# H_Bridge.net
KiCad netlist of a schematic drawn in Altium Designer
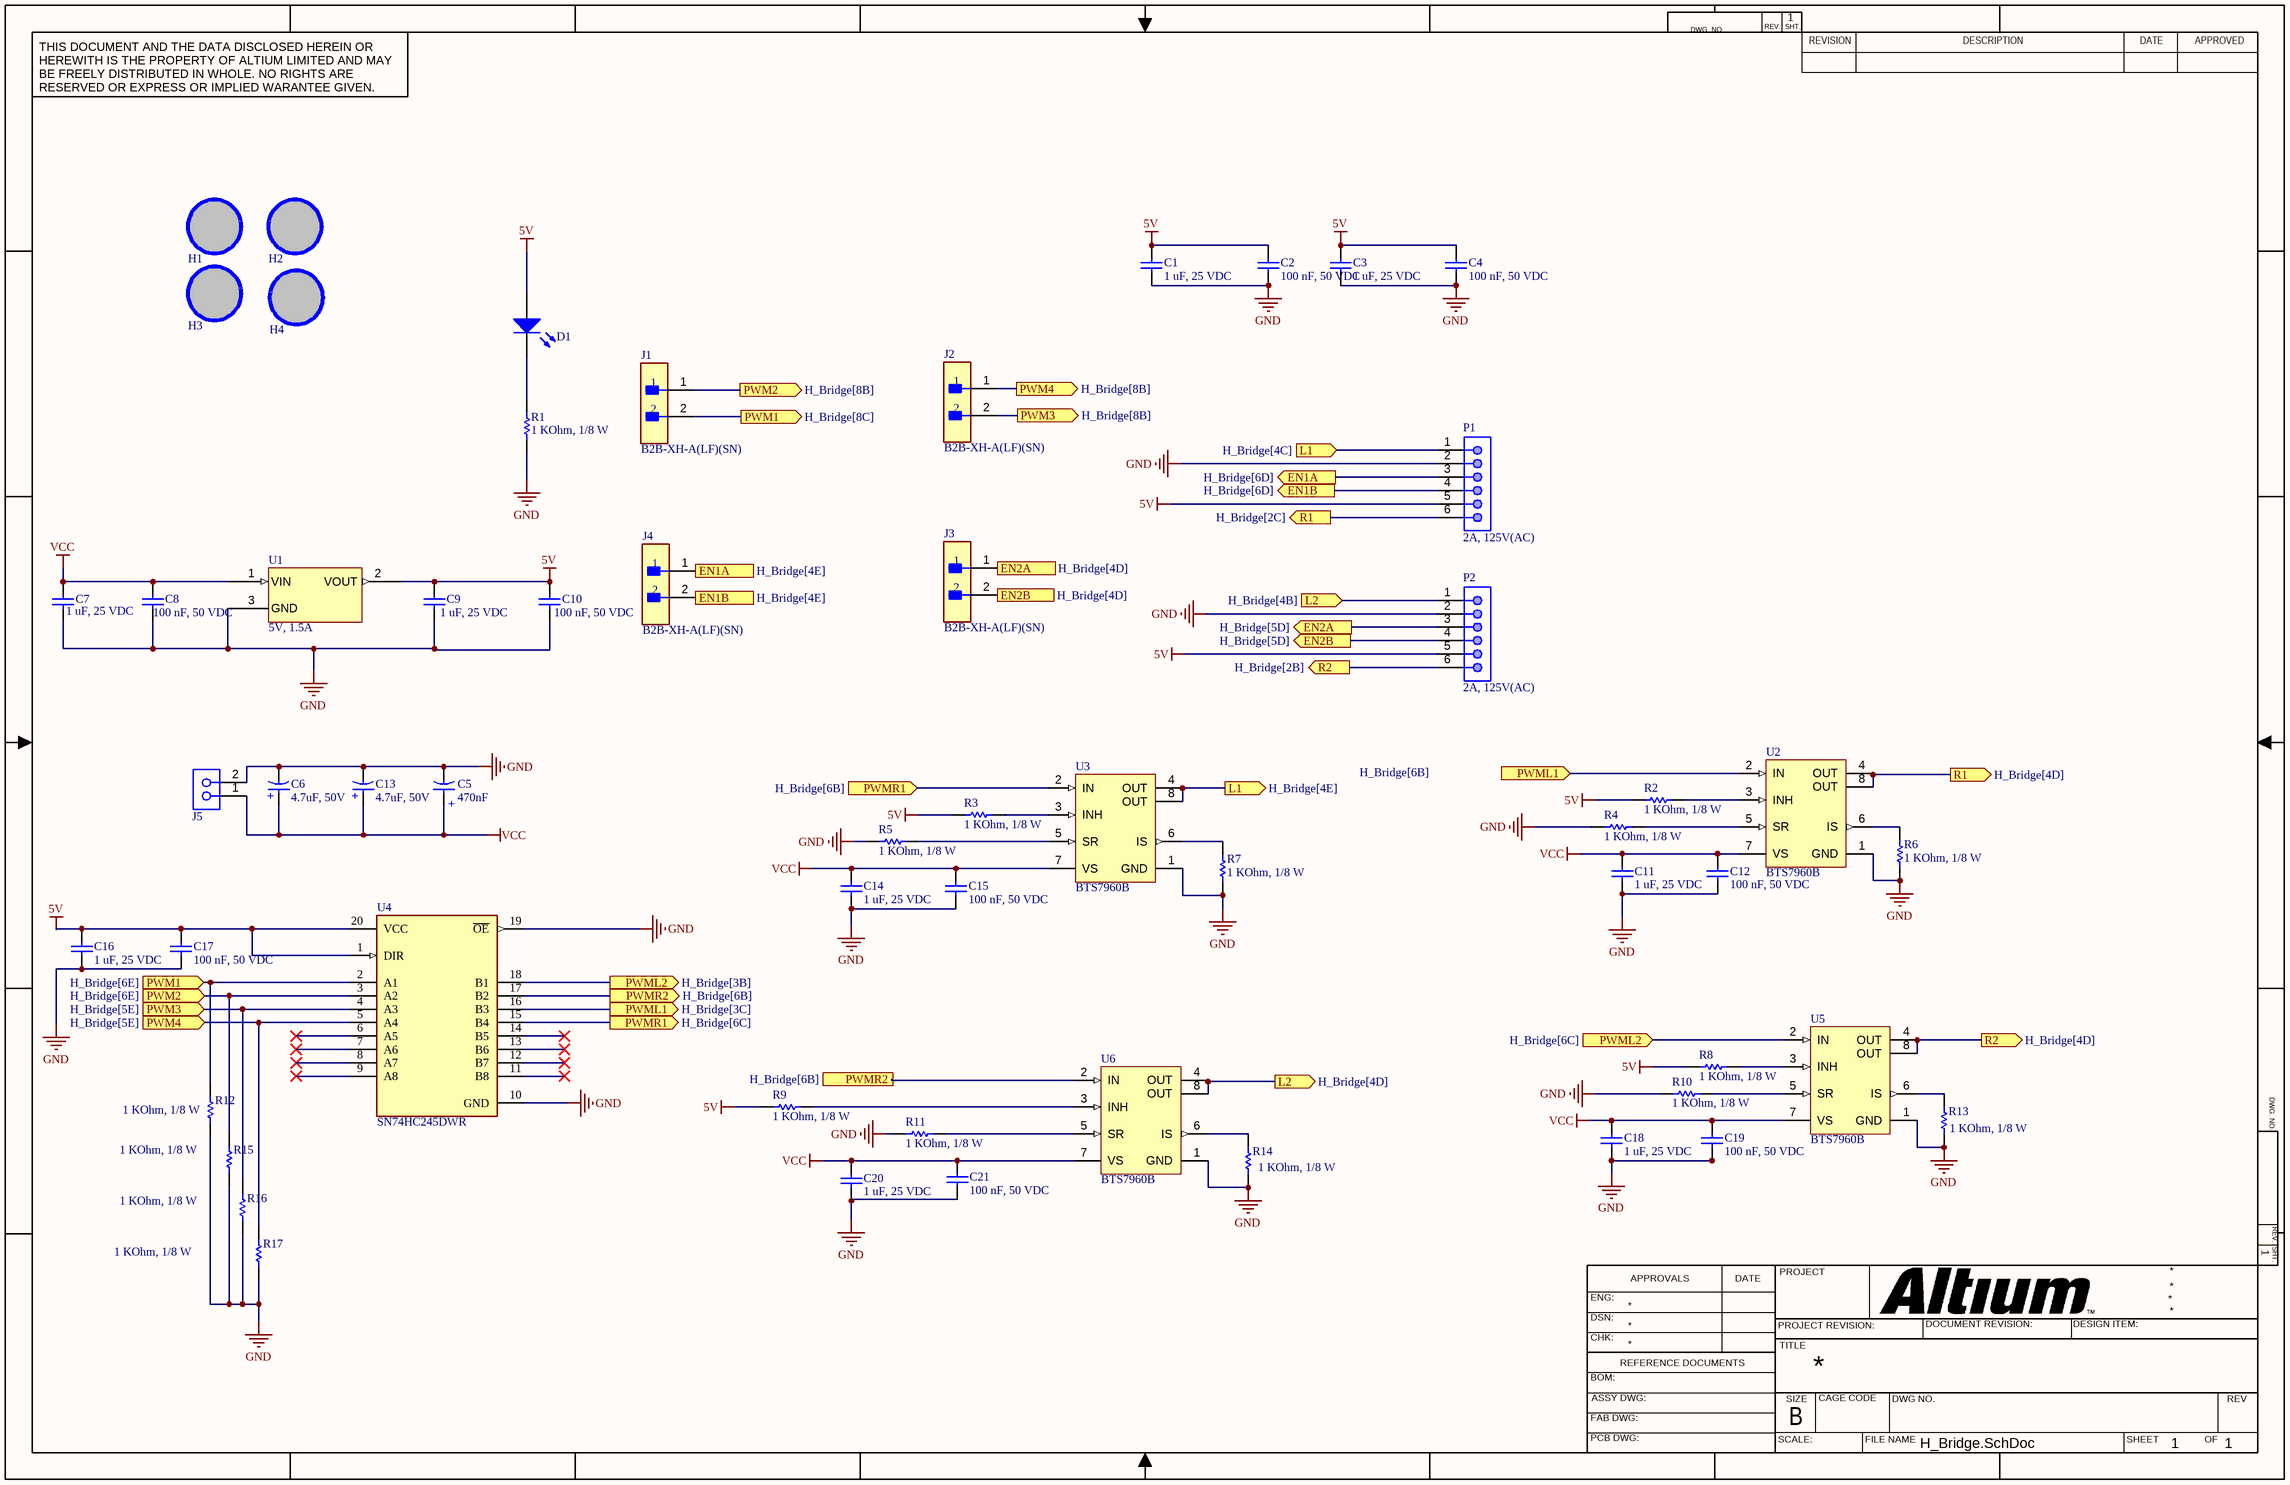
[diagram p0: H_Bridge.SchDoc]

(export (version "E")
  (design (tool "Eeschema 10.0.6"))
  (components
    (comp (ref "C1")
      (value "1 uF, 25 VDC")
      (footprint "CAP_0805")
      (description "CAP, size 0805, 1 uF, 25 VDC")
      (fields (field (name "TOLERANCE") "+/-10%"))
      (libsource (lib "Altium_Ceramic_Cap") (part "0108051051025"))
    )
    (comp (ref "C2")
      (value "100 nF, 50 VDC")
      (footprint "CAP_0805")
      (description "CAP, size 0805, 100 nF, 50 VDC")
      (fields (field (name "TOLERANCE") "+/-10%"))
      (libsource (lib "Altium_Ceramic_Cap") (part "0108051041050"))
    )
    (comp (ref "C3")
      (value "1 uF, 25 VDC")
      (footprint "CAP_0805")
      (description "CAP, size 0805, 1 uF, 25 VDC")
      (fields (field (name "TOLERANCE") "+/-10%"))
      (libsource (lib "Altium_Ceramic_Cap") (part "0108051051025"))
    )
    (comp (ref "C4")
      (value "100 nF, 50 VDC")
      (footprint "CAP_0805")
      (description "CAP, size 0805, 100 nF, 50 VDC")
      (fields (field (name "TOLERANCE") "+/-10%"))
      (libsource (lib "Altium_Ceramic_Cap") (part "0108051041050"))
    )
    (comp (ref "C5")
      (value "470nF")
      (footprint "WCAP-ASLU_D4H5.5")
      (description "865090640004 WCAP-ASLU Aluminum Electrolytic Capacitors")
      (fields (field (name "TOLERANCE") "20%"))
      (libsource (lib "Altium Content Vault") (part "Capacitor_Polarized"))
    )
    (comp (ref "C6")
      (value "4.7uF, 50V")
      (footprint "WCAP-ASLI_D4H5.5")
      (description "V-Chip, D4 x H5.5mm, 4.7uF, 50V")
      (fields (field (name "MANUFACTURER") "Wurth Elektronik"))
      (libsource (lib "Altium_Alutinum_Cap") (part "865080640004"))
    )
    (comp (ref "C7")
      (value "1 uF, 25 VDC")
      (footprint "CAP_0805")
      (description "CAP, size 0805, 1 uF, 25 VDC")
      (fields (field (name "TOLERANCE") "+/-10%"))
      (libsource (lib "Altium_Ceramic_Cap") (part "0108051051025"))
    )
    (comp (ref "C8")
      (value "100 nF, 50 VDC")
      (footprint "CAP_0805")
      (description "CAP, size 0805, 100 nF, 50 VDC")
      (fields (field (name "TOLERANCE") "+/-10%"))
      (libsource (lib "Altium_Ceramic_Cap") (part "0108051041050"))
    )
    (comp (ref "C9")
      (value "1 uF, 25 VDC")
      (footprint "CAP_0805")
      (description "CAP, size 0805, 1 uF, 25 VDC")
      (fields (field (name "TOLERANCE") "+/-10%"))
      (libsource (lib "Altium_Ceramic_Cap") (part "0108051051025"))
    )
    (comp (ref "C10")
      (value "100 nF, 50 VDC")
      (footprint "CAP_0805")
      (description "CAP, size 0805, 100 nF, 50 VDC")
      (fields (field (name "TOLERANCE") "+/-10%"))
      (libsource (lib "Altium_Ceramic_Cap") (part "0108051041050"))
    )
    (comp (ref "C11")
      (value "1 uF, 25 VDC")
      (footprint "CAP_0805")
      (description "CAP, size 0805, 1 uF, 25 VDC")
      (fields (field (name "TOLERANCE") "+/-10%"))
      (libsource (lib "Altium_Ceramic_Cap") (part "0108051051025"))
    )
    (comp (ref "C12")
      (value "100 nF, 50 VDC")
      (footprint "CAP_0805")
      (description "CAP, size 0805, 100 nF, 50 VDC")
      (fields (field (name "TOLERANCE") "+/-10%"))
      (libsource (lib "Altium_Ceramic_Cap") (part "0108051041050"))
    )
    (comp (ref "C13")
      (value "4.7uF, 50V")
      (footprint "WCAP-ASLI_D4H5.5")
      (description "V-Chip, D4 x H5.5mm, 4.7uF, 50V")
      (fields (field (name "MANUFACTURER") "Wurth Elektronik"))
      (libsource (lib "Altium_Alutinum_Cap") (part "865080640004"))
    )
    (comp (ref "C14")
      (value "1 uF, 25 VDC")
      (footprint "CAP_0805")
      (description "CAP, size 0805, 1 uF, 25 VDC")
      (fields (field (name "TOLERANCE") "+/-10%"))
      (libsource (lib "Altium_Ceramic_Cap") (part "0108051051025"))
    )
    (comp (ref "C15")
      (value "100 nF, 50 VDC")
      (footprint "CAP_0805")
      (description "CAP, size 0805, 100 nF, 50 VDC")
      (fields (field (name "TOLERANCE") "+/-10%"))
      (libsource (lib "Altium_Ceramic_Cap") (part "0108051041050"))
    )
    (comp (ref "C16")
      (value "1 uF, 25 VDC")
      (footprint "CAP_0805")
      (description "CAP, size 0805, 1 uF, 25 VDC")
      (fields (field (name "TOLERANCE") "+/-10%"))
      (libsource (lib "Altium_Ceramic_Cap") (part "0108051051025"))
    )
    (comp (ref "C17")
      (value "100 nF, 50 VDC")
      (footprint "CAP_0805")
      (description "CAP, size 0805, 100 nF, 50 VDC")
      (fields (field (name "TOLERANCE") "+/-10%"))
      (libsource (lib "Altium_Ceramic_Cap") (part "0108051041050"))
    )
    (comp (ref "C18")
      (value "1 uF, 25 VDC")
      (footprint "CAP_0805")
      (description "CAP, size 0805, 1 uF, 25 VDC")
      (fields (field (name "TOLERANCE") "+/-10%"))
      (libsource (lib "Altium_Ceramic_Cap") (part "0108051051025"))
    )
    (comp (ref "C19")
      (value "100 nF, 50 VDC")
      (footprint "CAP_0805")
      (description "CAP, size 0805, 100 nF, 50 VDC")
      (fields (field (name "TOLERANCE") "+/-10%"))
      (libsource (lib "Altium_Ceramic_Cap") (part "0108051041050"))
    )
    (comp (ref "C20")
      (value "1 uF, 25 VDC")
      (footprint "CAP_0805")
      (description "CAP, size 0805, 1 uF, 25 VDC")
      (fields (field (name "TOLERANCE") "+/-10%"))
      (libsource (lib "Altium_Ceramic_Cap") (part "0108051051025"))
    )
    (comp (ref "C21")
      (value "100 nF, 50 VDC")
      (footprint "CAP_0805")
      (description "CAP, size 0805, 100 nF, 50 VDC")
      (fields (field (name "TOLERANCE") "+/-10%"))
      (libsource (lib "Altium_Ceramic_Cap") (part "0108051041050"))
    )
    (comp (ref "D1")
      (value "LED SMD")
      (footprint "LED_0805_Blue")
      (description "LED")
      (libsource (lib "Board_C24") (part "LED SMD"))
    )
    (comp (ref "H1")
      (value "Hole")
      (footprint "LO KHOAN 3MM")
      (description "Hole 3mm")
      (libsource (lib "Board_C24") (part "Hole"))
    )
    (comp (ref "H2")
      (value "Hole")
      (footprint "LO KHOAN 3MM")
      (description "Hole 3mm")
      (libsource (lib "Board_C24") (part "Hole"))
    )
    (comp (ref "H3")
      (value "Hole")
      (footprint "LO KHOAN 3MM")
      (description "Hole 3mm")
      (libsource (lib "Board_C24") (part "Hole"))
    )
    (comp (ref "H4")
      (value "Hole")
      (footprint "LO KHOAN 3MM")
      (description "Hole 3mm")
      (libsource (lib "Board_C24") (part "Hole"))
    )
    (comp (ref "J1")
      (value "B2B-XH-A(LF)(SN)")
      (footprint "FP-B2B-XH-A_LF_SN-MFG")
      (description "CONN HEADER VERT 2POS 2.5MM")
      (libsource (lib "Altium Content Vault") (part "3bc925449376181038e59eaffc5286c"))
    )
    (comp (ref "J2")
      (value "B2B-XH-A(LF)(SN)")
      (footprint "FP-B2B-XH-A_LF_SN-MFG")
      (description "CONN HEADER VERT 2POS 2.5MM")
      (libsource (lib "Altium Content Vault") (part "3bc925449376181038e59eaffc5286c"))
    )
    (comp (ref "J3")
      (value "B2B-XH-A(LF)(SN)")
      (footprint "FP-B2B-XH-A_LF_SN-MFG")
      (description "CONN HEADER VERT 2POS 2.5MM")
      (libsource (lib "Altium Content Vault") (part "3bc925449376181038e59eaffc5286c"))
    )
    (comp (ref "J4")
      (value "B2B-XH-A(LF)(SN)")
      (footprint "FP-B2B-XH-A_LF_SN-MFG")
      (description "CONN HEADER VERT 2POS 2.5MM")
      (libsource (lib "Altium Content Vault") (part "3bc925449376181038e59eaffc5286c"))
    )
    (comp (ref "J5")
      (value "4A, 300V")
      (footprint "691418420002")
      (description "WR-TBL Series 4184 45° Entry, THT, pitch 7.62mm, 2p")
      (fields
        (field (name "MANUFACTURER PART NUMBER") "691418420002")
        (field (name "MANUFACTURER") "Wurth Elektronik")
      )
      (libsource (lib "Altium_Terminal_Block") (part "691418420002"))
    )
    (comp (ref "P1")
      (value "2A, 125V(AC)")
      (footprint "62000611622")
      (description "WR-WTB Male Vertical Shrouded Header, pitch 2mm, 6p")
      (fields (field (name "PART NUMBER") "62000611622") (field (name "PUBLISHER") "Wurth Elektronik"))
      (libsource (lib "Altium_PCB_Connector") (part "62000611622"))
    )
    (comp (ref "P2")
      (value "2A, 125V(AC)")
      (footprint "62000611622")
      (description "WR-WTB Male Vertical Shrouded Header, pitch 2mm, 6p")
      (fields (field (name "PART NUMBER") "62000611622") (field (name "PUBLISHER") "Wurth Elektronik"))
      (libsource (lib "Altium_PCB_Connector") (part "62000611622"))
    )
    (comp (ref "R1")
      (value "1 KOhm, 1/8 W")
      (footprint "RESISTOR_0805")
      (description "RES, size 0805, 1 KOhm, 1/8 W")
      (libsource (lib "Altium_Resistor") (part "0008051021"))
    )
    (comp (ref "R2")
      (value "1 KOhm, 1/8 W")
      (footprint "RESISTOR_0805")
      (description "RES, size 0805, 1 KOhm, 1/8 W")
      (libsource (lib "Altium_Resistor") (part "0008051021"))
    )
    (comp (ref "R3")
      (value "1 KOhm, 1/8 W")
      (footprint "RESISTOR_0805")
      (description "RES, size 0805, 1 KOhm, 1/8 W")
      (libsource (lib "Altium_Resistor") (part "0008051021"))
    )
    (comp (ref "R4")
      (value "1 KOhm, 1/8 W")
      (footprint "RESISTOR_0805")
      (description "RES, size 0805, 1 KOhm, 1/8 W")
      (libsource (lib "Altium_Resistor") (part "0008051021"))
    )
    (comp (ref "R5")
      (value "1 KOhm, 1/8 W")
      (footprint "RESISTOR_0805")
      (description "RES, size 0805, 1 KOhm, 1/8 W")
      (libsource (lib "Altium_Resistor") (part "0008051021"))
    )
    (comp (ref "R6")
      (value "1 KOhm, 1/8 W")
      (footprint "RESISTOR_0805")
      (description "RES, size 0805, 1 KOhm, 1/8 W")
      (libsource (lib "Altium_Resistor") (part "0008051021"))
    )
    (comp (ref "R7")
      (value "1 KOhm, 1/8 W")
      (footprint "RESISTOR_0805")
      (description "RES, size 0805, 1 KOhm, 1/8 W")
      (libsource (lib "Altium_Resistor") (part "0008051021"))
    )
    (comp (ref "R8")
      (value "1 KOhm, 1/8 W")
      (footprint "RESISTOR_0805")
      (description "RES, size 0805, 1 KOhm, 1/8 W")
      (libsource (lib "Altium_Resistor") (part "0008051021"))
    )
    (comp (ref "R9")
      (value "1 KOhm, 1/8 W")
      (footprint "RESISTOR_0805")
      (description "RES, size 0805, 1 KOhm, 1/8 W")
      (libsource (lib "Altium_Resistor") (part "0008051021"))
    )
    (comp (ref "R10")
      (value "1 KOhm, 1/8 W")
      (footprint "RESISTOR_0805")
      (description "RES, size 0805, 1 KOhm, 1/8 W")
      (libsource (lib "Altium_Resistor") (part "0008051021"))
    )
    (comp (ref "R11")
      (value "1 KOhm, 1/8 W")
      (footprint "RESISTOR_0805")
      (description "RES, size 0805, 1 KOhm, 1/8 W")
      (libsource (lib "Altium_Resistor") (part "0008051021"))
    )
    (comp (ref "R12")
      (value "1 KOhm, 1/8 W")
      (footprint "RESISTOR_0805")
      (description "RES, size 0805, 1 KOhm, 1/8 W")
      (libsource (lib "Altium_Resistor") (part "0008051021"))
    )
    (comp (ref "R13")
      (value "1 KOhm, 1/8 W")
      (footprint "RESISTOR_0805")
      (description "RES, size 0805, 1 KOhm, 1/8 W")
      (libsource (lib "Altium_Resistor") (part "0008051021"))
    )
    (comp (ref "R14")
      (value "1 KOhm, 1/8 W")
      (footprint "RESISTOR_0805")
      (description "RES, size 0805, 1 KOhm, 1/8 W")
      (libsource (lib "Altium_Resistor") (part "0008051021"))
    )
    (comp (ref "R15")
      (value "1 KOhm, 1/8 W")
      (footprint "RESISTOR_0805")
      (description "RES, size 0805, 1 KOhm, 1/8 W")
      (libsource (lib "Altium_Resistor") (part "0008051021"))
    )
    (comp (ref "R16")
      (value "1 KOhm, 1/8 W")
      (footprint "RESISTOR_0805")
      (description "RES, size 0805, 1 KOhm, 1/8 W")
      (libsource (lib "Altium_Resistor") (part "0008051021"))
    )
    (comp (ref "R17")
      (value "1 KOhm, 1/8 W")
      (footprint "RESISTOR_0805")
      (description "RES, size 0805, 1 KOhm, 1/8 W")
      (libsource (lib "Altium_Resistor") (part "0008051021"))
    )
    (comp (ref "U1")
      (value "5V, 1.5A")
      (footprint "TO-263")
      (description "Out: 5V, 1.5A; In: 7V to 35V; Pacakge: TO-263")
      (libsource (lib "Altium_Power_Supply_IC") (part "L7805ACD2T_TO-263"))
    )
    (comp (ref "U2")
      (value "BTS7960B")
      (footprint "INF-P-TO-263-7-6_M")
      (description "High Current PN Half Bridge NovalithIC, -40 to 150 degC, P-TO-263-7-6")
      (fields (field (name "MANUFACTURER") "Infineon"))
      (libsource (lib "Altium Content Vault") (part "INF-BTS7960B-P-TO-263-7-8"))
    )
    (comp (ref "U3")
      (value "BTS7960B")
      (footprint "INF-P-TO-263-7-6_M")
      (description "High Current PN Half Bridge NovalithIC, -40 to 150 degC, P-TO-263-7-6")
      (fields (field (name "MANUFACTURER") "Infineon"))
      (libsource (lib "Altium Content Vault") (part "INF-BTS7960B-P-TO-263-7-8"))
    )
    (comp (ref "U4")
      (value "SN74HC245DWR")
      (footprint "FP-DW0020A-IPC_A")
      (description "IC TRANSCVR NON-INVERT 6V 20SOIC")
      (libsource (lib "Altium Content Vault") (part "88901bc343d40937cf0e66f0656714f"))
    )
    (comp (ref "U5")
      (value "BTS7960B")
      (footprint "INF-P-TO-263-7-6_M")
      (description "High Current PN Half Bridge NovalithIC, -40 to 150 degC, P-TO-263-7-6")
      (fields (field (name "MANUFACTURER") "Infineon"))
      (libsource (lib "Altium Content Vault") (part "INF-BTS7960B-P-TO-263-7-8"))
    )
    (comp (ref "U6")
      (value "BTS7960B")
      (footprint "INF-P-TO-263-7-6_M")
      (description "High Current PN Half Bridge NovalithIC, -40 to 150 degC, P-TO-263-7-6")
      (fields (field (name "MANUFACTURER") "Infineon"))
      (libsource (lib "Altium Content Vault") (part "INF-BTS7960B-P-TO-263-7-8"))
    )
  )
  (nets
    (net (code "1") (name "/EN1A") (class "Default")
      (node (ref "J4") (pin "1") (pinfunction "1_1") (pintype "passive"))
      (node (ref "P1") (pin "3") (pinfunction "3_3") (pintype "passive"))
    )
    (net (code "2") (name "/EN1B") (class "Default")
      (node (ref "J4") (pin "2") (pinfunction "2_2") (pintype "passive"))
      (node (ref "P1") (pin "4") (pinfunction "4_4") (pintype "passive"))
    )
    (net (code "3") (name "/EN2A") (class "Default")
      (node (ref "J3") (pin "1") (pinfunction "1_1") (pintype "passive"))
      (node (ref "P2") (pin "3") (pinfunction "3_3") (pintype "passive"))
    )
    (net (code "4") (name "/EN2B") (class "Default")
      (node (ref "J3") (pin "2") (pinfunction "2_2") (pintype "passive"))
      (node (ref "P2") (pin "4") (pinfunction "4_4") (pintype "passive"))
    )
    (net (code "5") (name "/L1") (class "Default")
      (node (ref "P1") (pin "1") (pinfunction "1_1") (pintype "passive"))
      (node (ref "U3") (pin "4") (pinfunction "OUT_4") (pintype "power_in"))
      (node (ref "U3") (pin "8") (pinfunction "OUT_8") (pintype "power_in"))
    )
    (net (code "6") (name "/L2") (class "Default")
      (node (ref "P2") (pin "1") (pinfunction "1_1") (pintype "passive"))
      (node (ref "U6") (pin "4") (pinfunction "OUT_4") (pintype "power_in"))
      (node (ref "U6") (pin "8") (pinfunction "OUT_8") (pintype "power_in"))
    )
    (net (code "7") (name "/PWM1") (class "Default")
      (node (ref "J1") (pin "2") (pinfunction "2_2") (pintype "passive"))
      (node (ref "R12") (pin "2") (pinfunction "2_2") (pintype "passive"))
      (node (ref "U4") (pin "2") (pinfunction "A1_2") (pintype "passive"))
    )
    (net (code "8") (name "/PWM2") (class "Default")
      (node (ref "J1") (pin "1") (pinfunction "1_1") (pintype "passive"))
      (node (ref "R15") (pin "2") (pinfunction "2_2") (pintype "passive"))
      (node (ref "U4") (pin "3") (pinfunction "A2_3") (pintype "passive"))
    )
    (net (code "9") (name "/PWM3") (class "Default")
      (node (ref "J2") (pin "2") (pinfunction "2_2") (pintype "passive"))
      (node (ref "R16") (pin "2") (pinfunction "2_2") (pintype "passive"))
      (node (ref "U4") (pin "4") (pinfunction "A3_4") (pintype "passive"))
    )
    (net (code "10") (name "/PWM4") (class "Default")
      (node (ref "J2") (pin "1") (pinfunction "1_1") (pintype "passive"))
      (node (ref "R17") (pin "2") (pinfunction "2_2") (pintype "passive"))
      (node (ref "U4") (pin "5") (pinfunction "A4_5") (pintype "passive"))
    )
    (net (code "11") (name "/PWML1") (class "Default")
      (node (ref "U2") (pin "2") (pinfunction "IN_2") (pintype "input"))
      (node (ref "U4") (pin "16") (pinfunction "B3_16") (pintype "passive"))
    )
    (net (code "12") (name "/PWML2") (class "Default")
      (node (ref "U4") (pin "18") (pinfunction "B1_18") (pintype "passive"))
      (node (ref "U5") (pin "2") (pinfunction "IN_2") (pintype "input"))
    )
    (net (code "13") (name "/PWMR1") (class "Default")
      (node (ref "U3") (pin "2") (pinfunction "IN_2") (pintype "input"))
      (node (ref "U4") (pin "15") (pinfunction "B4_15") (pintype "passive"))
    )
    (net (code "14") (name "/PWMR2") (class "Default")
      (node (ref "U4") (pin "17") (pinfunction "B2_17") (pintype "passive"))
    )
    (net (code "15") (name "/R1") (class "Default")
      (node (ref "P1") (pin "6") (pinfunction "6_6") (pintype "passive"))
      (node (ref "U2") (pin "4") (pinfunction "OUT_4") (pintype "power_in"))
      (node (ref "U2") (pin "8") (pinfunction "OUT_8") (pintype "power_in"))
    )
    (net (code "16") (name "/R2") (class "Default")
      (node (ref "P2") (pin "6") (pinfunction "6_6") (pintype "passive"))
      (node (ref "U5") (pin "4") (pinfunction "OUT_4") (pintype "power_in"))
      (node (ref "U5") (pin "8") (pinfunction "OUT_8") (pintype "power_in"))
    )
    (net (code "17") (name "5V") (class "Default")
      (node (ref "C1") (pin "2") (pinfunction "2_2") (pintype "passive"))
      (node (ref "C10") (pin "2") (pinfunction "2_2") (pintype "passive"))
      (node (ref "C16") (pin "2") (pinfunction "2_2") (pintype "passive"))
      (node (ref "C17") (pin "2") (pinfunction "2_2") (pintype "passive"))
      (node (ref "C2") (pin "2") (pinfunction "2_2") (pintype "passive"))
      (node (ref "C3") (pin "2") (pinfunction "2_2") (pintype "passive"))
      (node (ref "C4") (pin "2") (pinfunction "2_2") (pintype "passive"))
      (node (ref "C9") (pin "2") (pinfunction "2_2") (pintype "passive"))
      (node (ref "D1") (pin "1") (pinfunction "A_1") (pintype "passive"))
      (node (ref "P1") (pin "5") (pinfunction "5_5") (pintype "passive"))
      (node (ref "P2") (pin "5") (pinfunction "5_5") (pintype "passive"))
      (node (ref "R2") (pin "2") (pinfunction "2_2") (pintype "passive"))
      (node (ref "R3") (pin "2") (pinfunction "2_2") (pintype "passive"))
      (node (ref "R8") (pin "2") (pinfunction "2_2") (pintype "passive"))
      (node (ref "R9") (pin "2") (pinfunction "2_2") (pintype "passive"))
      (node (ref "U1") (pin "2") (pinfunction "VOUT_2") (pintype "output"))
      (node (ref "U4") (pin "1") (pinfunction "DIR_1") (pintype "input"))
      (node (ref "U4") (pin "20") (pinfunction "VCC_20") (pintype "open_emitter"))
    )
    (net (code "18") (name "GND") (class "Default")
      (node (ref "C1") (pin "1") (pinfunction "1_1") (pintype "passive"))
      (node (ref "C10") (pin "1") (pinfunction "1_1") (pintype "passive"))
      (node (ref "C11") (pin "1") (pinfunction "1_1") (pintype "passive"))
      (node (ref "C12") (pin "1") (pinfunction "1_1") (pintype "passive"))
      (node (ref "C13") (pin "2") (pinfunction "N_2") (pintype "passive"))
      (node (ref "C14") (pin "1") (pinfunction "1_1") (pintype "passive"))
      (node (ref "C15") (pin "1") (pinfunction "1_1") (pintype "passive"))
      (node (ref "C16") (pin "1") (pinfunction "1_1") (pintype "passive"))
      (node (ref "C17") (pin "1") (pinfunction "1_1") (pintype "passive"))
      (node (ref "C18") (pin "1") (pinfunction "1_1") (pintype "passive"))
      (node (ref "C19") (pin "1") (pinfunction "1_1") (pintype "passive"))
      (node (ref "C2") (pin "1") (pinfunction "1_1") (pintype "passive"))
      (node (ref "C20") (pin "1") (pinfunction "1_1") (pintype "passive"))
      (node (ref "C21") (pin "1") (pinfunction "1_1") (pintype "passive"))
      (node (ref "C3") (pin "1") (pinfunction "1_1") (pintype "passive"))
      (node (ref "C4") (pin "1") (pinfunction "1_1") (pintype "passive"))
      (node (ref "C5") (pin "2") (pinfunction "N_2") (pintype "passive"))
      (node (ref "C6") (pin "2") (pinfunction "N_2") (pintype "passive"))
      (node (ref "C7") (pin "1") (pinfunction "1_1") (pintype "passive"))
      (node (ref "C8") (pin "1") (pinfunction "1_1") (pintype "passive"))
      (node (ref "C9") (pin "1") (pinfunction "1_1") (pintype "passive"))
      (node (ref "J5") (pin "2") (pinfunction "2_2") (pintype "passive"))
      (node (ref "P1") (pin "2") (pinfunction "2_2") (pintype "passive"))
      (node (ref "P2") (pin "2") (pinfunction "2_2") (pintype "passive"))
      (node (ref "R1") (pin "2") (pinfunction "2_2") (pintype "passive"))
      (node (ref "R10") (pin "2") (pinfunction "2_2") (pintype "passive"))
      (node (ref "R11") (pin "2") (pinfunction "2_2") (pintype "passive"))
      (node (ref "R12") (pin "1") (pinfunction "1_1") (pintype "passive"))
      (node (ref "R13") (pin "1") (pinfunction "1_1") (pintype "passive"))
      (node (ref "R14") (pin "1") (pinfunction "1_1") (pintype "passive"))
      (node (ref "R15") (pin "1") (pinfunction "1_1") (pintype "passive"))
      (node (ref "R16") (pin "1") (pinfunction "1_1") (pintype "passive"))
      (node (ref "R17") (pin "1") (pinfunction "1_1") (pintype "passive"))
      (node (ref "R4") (pin "2") (pinfunction "2_2") (pintype "passive"))
      (node (ref "R5") (pin "2") (pinfunction "2_2") (pintype "passive"))
      (node (ref "R6") (pin "2") (pinfunction "2_2") (pintype "passive"))
      (node (ref "R7") (pin "2") (pinfunction "2_2") (pintype "passive"))
      (node (ref "U1") (pin "3") (pinfunction "GND_3") (pintype "passive"))
      (node (ref "U2") (pin "1") (pinfunction "GND_1") (pintype "power_in"))
      (node (ref "U3") (pin "1") (pinfunction "GND_1") (pintype "power_in"))
      (node (ref "U4") (pin "10") (pinfunction "GND_10") (pintype "power_in"))
      (node (ref "U4") (pin "19") (pinfunction "~{OE}_19") (pintype "output"))
      (node (ref "U5") (pin "1") (pinfunction "GND_1") (pintype "power_in"))
      (node (ref "U6") (pin "1") (pinfunction "GND_1") (pintype "power_in"))
    )
    (net (code "19") (name "Net-(D1-K)") (class "Default")
      (node (ref "D1") (pin "2") (pinfunction "K_2") (pintype "passive"))
      (node (ref "R1") (pin "1") (pinfunction "1_1") (pintype "passive"))
    )
    (net (code "20") (name "Net-(U2-INH)") (class "Default")
      (node (ref "R2") (pin "1") (pinfunction "1_1") (pintype "passive"))
      (node (ref "U2") (pin "3") (pinfunction "INH_3") (pintype "input"))
    )
    (net (code "21") (name "Net-(U2-IS)") (class "Default")
      (node (ref "R6") (pin "1") (pinfunction "1_1") (pintype "passive"))
      (node (ref "U2") (pin "6") (pinfunction "IS_6") (pintype "output"))
    )
    (net (code "22") (name "Net-(U2-SR)") (class "Default")
      (node (ref "R4") (pin "1") (pinfunction "1_1") (pintype "passive"))
      (node (ref "U2") (pin "5") (pinfunction "SR_5") (pintype "input"))
    )
    (net (code "23") (name "Net-(U3-INH)") (class "Default")
      (node (ref "R3") (pin "1") (pinfunction "1_1") (pintype "passive"))
      (node (ref "U3") (pin "3") (pinfunction "INH_3") (pintype "input"))
    )
    (net (code "24") (name "Net-(U3-IS)") (class "Default")
      (node (ref "R7") (pin "1") (pinfunction "1_1") (pintype "passive"))
      (node (ref "U3") (pin "6") (pinfunction "IS_6") (pintype "output"))
    )
    (net (code "25") (name "Net-(U3-SR)") (class "Default")
      (node (ref "R5") (pin "1") (pinfunction "1_1") (pintype "passive"))
      (node (ref "U3") (pin "5") (pinfunction "SR_5") (pintype "input"))
    )
    (net (code "26") (name "Net-(U5-INH)") (class "Default")
      (node (ref "R8") (pin "1") (pinfunction "1_1") (pintype "passive"))
      (node (ref "U5") (pin "3") (pinfunction "INH_3") (pintype "input"))
    )
    (net (code "27") (name "Net-(U5-IS)") (class "Default")
      (node (ref "R13") (pin "2") (pinfunction "2_2") (pintype "passive"))
      (node (ref "U5") (pin "6") (pinfunction "IS_6") (pintype "output"))
    )
    (net (code "28") (name "Net-(U5-SR)") (class "Default")
      (node (ref "R10") (pin "1") (pinfunction "1_1") (pintype "passive"))
      (node (ref "U5") (pin "5") (pinfunction "SR_5") (pintype "input"))
    )
    (net (code "29") (name "Net-(U6-INH)") (class "Default")
      (node (ref "R9") (pin "1") (pinfunction "1_1") (pintype "passive"))
      (node (ref "U6") (pin "3") (pinfunction "INH_3") (pintype "input"))
    )
    (net (code "30") (name "Net-(U6-IS)") (class "Default")
      (node (ref "R14") (pin "2") (pinfunction "2_2") (pintype "passive"))
      (node (ref "U6") (pin "6") (pinfunction "IS_6") (pintype "output"))
    )
    (net (code "31") (name "Net-(U6-SR)") (class "Default")
      (node (ref "R11") (pin "1") (pinfunction "1_1") (pintype "passive"))
      (node (ref "U6") (pin "5") (pinfunction "SR_5") (pintype "input"))
    )
    (net (code "32") (name "VCC") (class "Default")
      (node (ref "C11") (pin "2") (pinfunction "2_2") (pintype "passive"))
      (node (ref "C12") (pin "2") (pinfunction "2_2") (pintype "passive"))
      (node (ref "C13") (pin "1") (pinfunction "P_1") (pintype "passive"))
      (node (ref "C14") (pin "2") (pinfunction "2_2") (pintype "passive"))
      (node (ref "C15") (pin "2") (pinfunction "2_2") (pintype "passive"))
      (node (ref "C18") (pin "2") (pinfunction "2_2") (pintype "passive"))
      (node (ref "C19") (pin "2") (pinfunction "2_2") (pintype "passive"))
      (node (ref "C20") (pin "2") (pinfunction "2_2") (pintype "passive"))
      (node (ref "C21") (pin "2") (pinfunction "2_2") (pintype "passive"))
      (node (ref "C5") (pin "1") (pinfunction "P_1") (pintype "passive"))
      (node (ref "C6") (pin "1") (pinfunction "P_1") (pintype "passive"))
      (node (ref "C7") (pin "2") (pinfunction "2_2") (pintype "passive"))
      (node (ref "C8") (pin "2") (pinfunction "2_2") (pintype "passive"))
      (node (ref "J5") (pin "1") (pinfunction "1_1") (pintype "passive"))
      (node (ref "U1") (pin "1") (pinfunction "VIN_1") (pintype "input"))
      (node (ref "U2") (pin "7") (pinfunction "VS_7") (pintype "power_in"))
      (node (ref "U3") (pin "7") (pinfunction "VS_7") (pintype "power_in"))
      (node (ref "U5") (pin "7") (pinfunction "VS_7") (pintype "power_in"))
      (node (ref "U6") (pin "7") (pinfunction "VS_7") (pintype "power_in"))
    )
    (net (code "33") (name "unconnected-(H1-Pad1)") (class "Default")
      (node (ref "H1") (pin "1") (pinfunction "1_1") (pintype "passive"))
    )
    (net (code "34") (name "unconnected-(H2-Pad1)") (class "Default")
      (node (ref "H2") (pin "1") (pinfunction "1_1") (pintype "passive"))
    )
    (net (code "35") (name "unconnected-(H3-Pad1)") (class "Default")
      (node (ref "H3") (pin "1") (pinfunction "1_1") (pintype "passive"))
    )
    (net (code "36") (name "unconnected-(H4-Pad1)") (class "Default")
      (node (ref "H4") (pin "1") (pinfunction "1_1") (pintype "passive"))
    )
    (net (code "37") (name "unconnected-(U4-A5-Pad6)") (class "Default")
      (node (ref "U4") (pin "6") (pinfunction "A5_6") (pintype "passive+no_connect"))
    )
    (net (code "38") (name "unconnected-(U4-A6-Pad7)") (class "Default")
      (node (ref "U4") (pin "7") (pinfunction "A6_7") (pintype "passive+no_connect"))
    )
    (net (code "39") (name "unconnected-(U4-A7-Pad8)") (class "Default")
      (node (ref "U4") (pin "8") (pinfunction "A7_8") (pintype "passive+no_connect"))
    )
    (net (code "40") (name "unconnected-(U4-A8-Pad9)") (class "Default")
      (node (ref "U4") (pin "9") (pinfunction "A8_9") (pintype "passive+no_connect"))
    )
    (net (code "41") (name "unconnected-(U4-B5-Pad14)") (class "Default")
      (node (ref "U4") (pin "14") (pinfunction "B5_14") (pintype "passive+no_connect"))
    )
    (net (code "42") (name "unconnected-(U4-B6-Pad13)") (class "Default")
      (node (ref "U4") (pin "13") (pinfunction "B6_13") (pintype "passive+no_connect"))
    )
    (net (code "43") (name "unconnected-(U4-B7-Pad12)") (class "Default")
      (node (ref "U4") (pin "12") (pinfunction "B7_12") (pintype "passive+no_connect"))
    )
    (net (code "44") (name "unconnected-(U4-B8-Pad11)") (class "Default")
      (node (ref "U4") (pin "11") (pinfunction "B8_11") (pintype "passive+no_connect"))
    )
    (net (code "45") (name "unconnected-(U6-IN-Pad2)") (class "Default")
      (node (ref "U6") (pin "2") (pinfunction "IN_2") (pintype "input"))
    )
  )
)
